# Examples.net
KiCad netlist of a schematic drawn in EAGLE
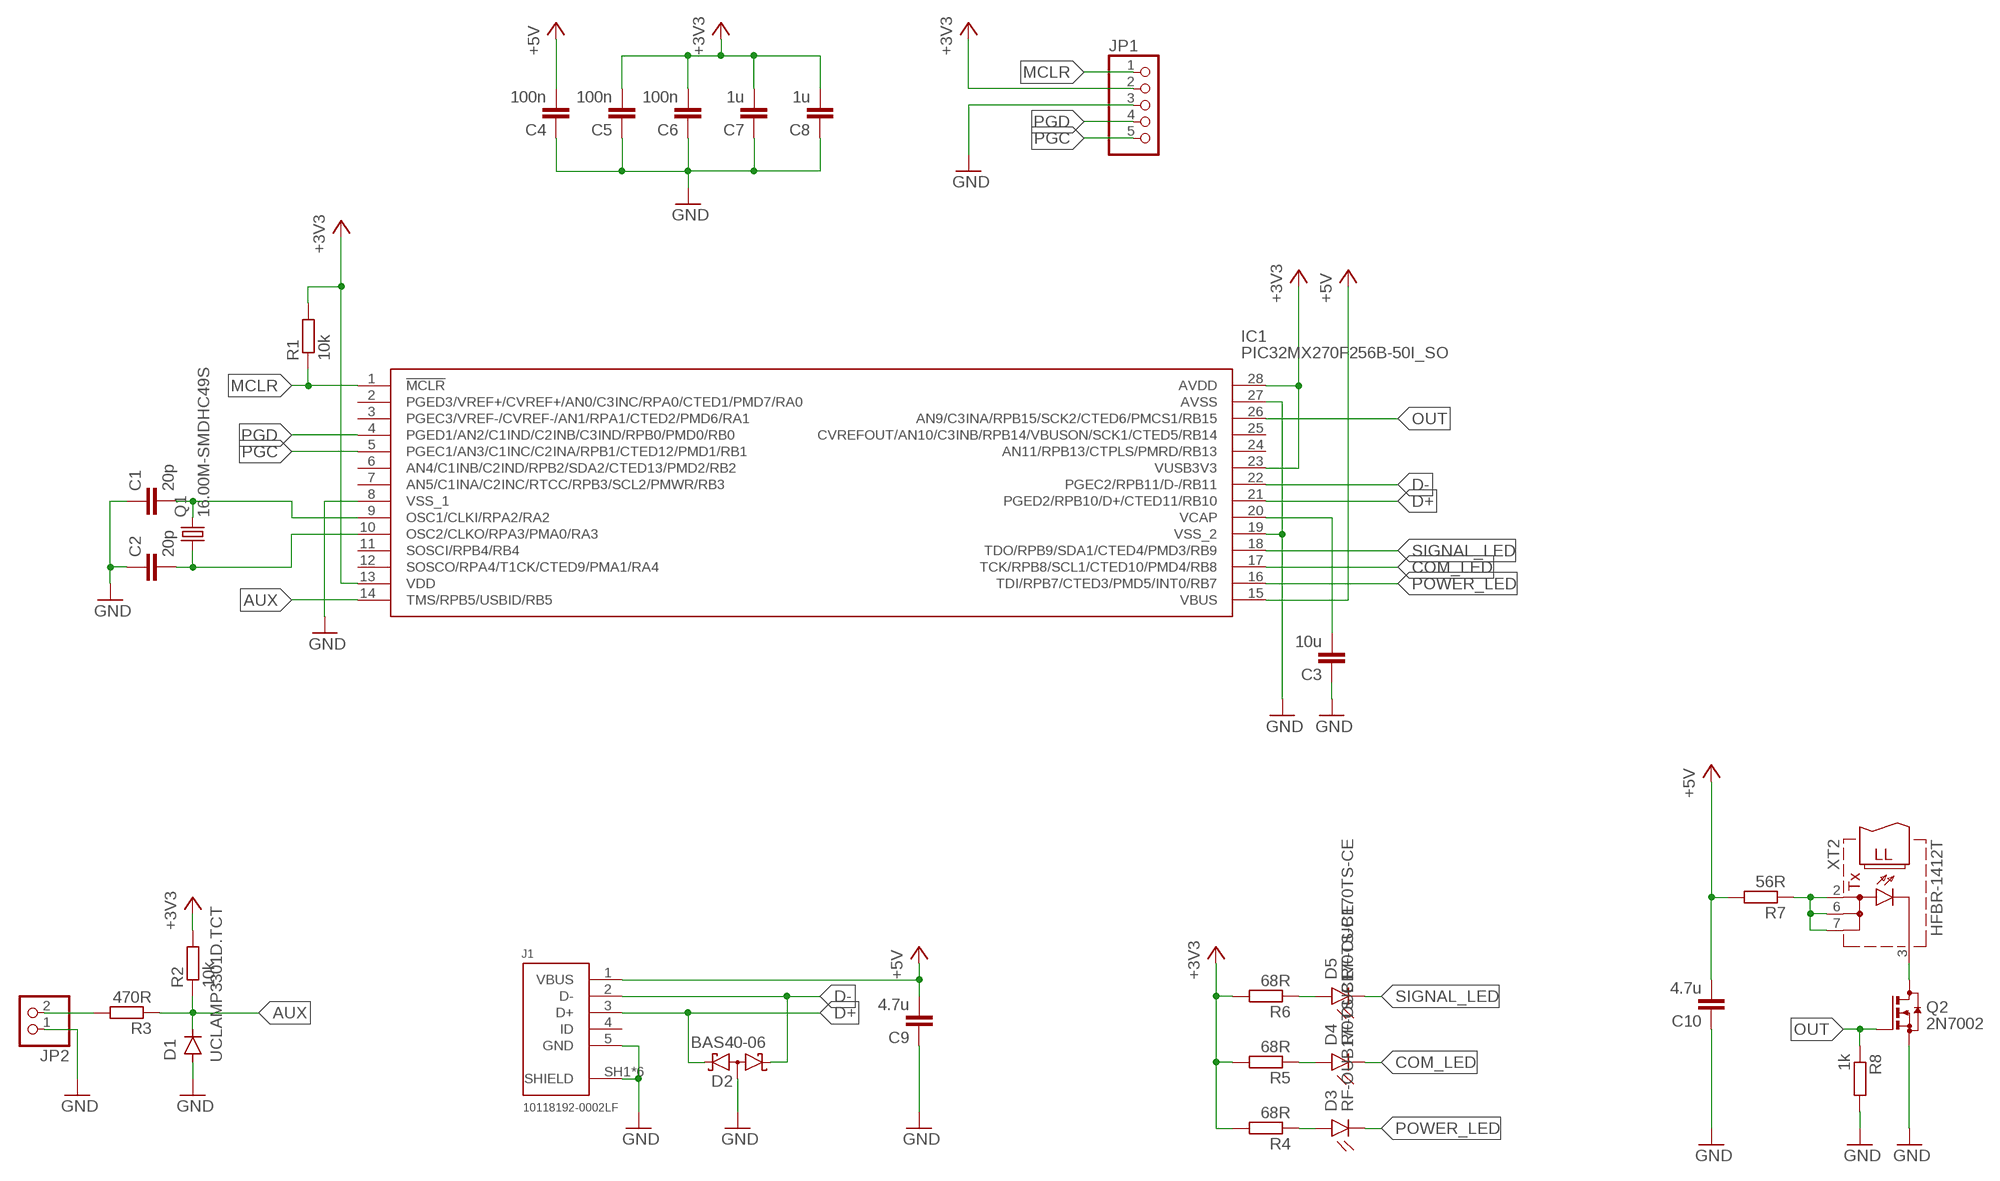
[diagram p0: schematic, sheet 1]

(export (version "E")
  (design (tool "Eeschema 10.0.6"))
  (components
    (comp (ref "C1")
      (value "20p")
      (footprint "eagle-import:C0805")
      (libsource (lib "eagle-import") (part "C-EUC0805"))
    )
    (comp (ref "C2")
      (value "20p")
      (footprint "eagle-import:C0805")
      (libsource (lib "eagle-import") (part "C-EUC0805"))
    )
    (comp (ref "C3")
      (value "10u")
      (footprint "eagle-import:C0805")
      (libsource (lib "eagle-import") (part "C-EUC0805"))
    )
    (comp (ref "C4")
      (value "100n")
      (footprint "eagle-import:C0805")
      (libsource (lib "eagle-import") (part "C-EUC0805"))
    )
    (comp (ref "C5")
      (value "100n")
      (footprint "eagle-import:C0805")
      (libsource (lib "eagle-import") (part "C-EUC0805"))
    )
    (comp (ref "C6")
      (value "100n")
      (footprint "eagle-import:C0805")
      (libsource (lib "eagle-import") (part "C-EUC0805"))
    )
    (comp (ref "C7")
      (value "1u")
      (footprint "eagle-import:C0805")
      (libsource (lib "eagle-import") (part "C-EUC0805"))
    )
    (comp (ref "C8")
      (value "1u")
      (footprint "eagle-import:C0805")
      (libsource (lib "eagle-import") (part "C-EUC0805"))
    )
    (comp (ref "C9")
      (value "4.7u")
      (footprint "eagle-import:C0805")
      (libsource (lib "eagle-import") (part "C-EUC0805"))
    )
    (comp (ref "C10")
      (value "4.7u")
      (footprint "eagle-import:C0805")
      (libsource (lib "eagle-import") (part "C-EUC0805"))
    )
    (comp (ref "D1")
      (value "UCLAMP3301D.TCT")
      (footprint "eagle-import:SOD-323")
      (fields
        (field (name "DIGIKEY_PART_NUMBER") "1N4148WSFSTR-ND")
        (field (name "MANUFACTURER") "Diodes Incorporated")
        (field (name "MPN") "1N4148WS")
        (field (name "CREATED_BY") "PCBLayout.com")
      )
      (libsource (lib "eagle-import") (part "1N4148WS"))
    )
    (comp (ref "D2")
      (value "BAS40-06")
      (footprint "eagle-import:SOT23")
      (libsource (lib "eagle-import") (part "BAS40-06"))
    )
    (comp (ref "D3")
      (value "RF-OUB170TS-CE")
      (footprint "eagle-import:LEDC2012X110N_FLAT-B")
      (libsource (lib "eagle-import") (part "CHIP-FLAT-B_0805"))
    )
    (comp (ref "D4")
      (value "RF-OUB170TS-CE")
      (footprint "eagle-import:LEDC2012X110N_FLAT-B")
      (libsource (lib "eagle-import") (part "CHIP-FLAT-B_0805"))
    )
    (comp (ref "D5")
      (value "RF-OUB170TS-CE")
      (footprint "eagle-import:LEDC2012X110N_FLAT-B")
      (libsource (lib "eagle-import") (part "CHIP-FLAT-B_0805"))
    )
    (comp (ref "IC1")
      (value "PIC32MX270F256B-50I_SO")
      (footprint "eagle-import:SOIC127P1030X265-28N")
      (fields
        (field (name "MANUFACTURER_PART_NUMBER") "PIC32MX270F256B-50I/SO")
        (field (name "MOUSER_PART_NUMBER") "579-32MX270F256B5ISO")
      )
      (libsource (lib "eagle-import") (part "PIC32MX270F256B-50I_SO"))
    )
    (comp (ref "J1")
      (value "10118192-0002LF")
      (footprint "eagle-import:10118192-0002LF")
      (fields
        (field (name "DIGIKEY_PARTNO") "609-5379-2-ND")
        (field (name "MANUFACTURER") "Amphenol ICC (FCI)")
        (field (name "CREATED_BY") "PCBLayout.com")
      )
      (libsource (lib "eagle-import") (part "10118192-0002LF"))
    )
    (comp (ref "JP1")
      (value "PINHD-1X5")
      (footprint "eagle-import:1X05")
      (libsource (lib "eagle-import") (part "PINHD-1X5"))
    )
    (comp (ref "JP2")
      (value "PINHD-1X2")
      (footprint "eagle-import:1X02")
      (libsource (lib "eagle-import") (part "PINHD-1X2"))
    )
    (comp (ref "Q1")
      (value "16.00M-SMDHC49S")
      (footprint "eagle-import:SM49")
      (libsource (lib "eagle-import") (part "CRYSTALSM49"))
    )
    (comp (ref "Q2")
      (value "2N7002")
      (footprint "eagle-import:SOT23")
      (libsource (lib "eagle-import") (part "BSS123"))
    )
    (comp (ref "R1")
      (value "10k")
      (footprint "eagle-import:R0805")
      (libsource (lib "eagle-import") (part "R-EU_R0805"))
    )
    (comp (ref "R2")
      (value "10k")
      (footprint "eagle-import:R0805")
      (libsource (lib "eagle-import") (part "R-EU_R0805"))
    )
    (comp (ref "R3")
      (value "470R")
      (footprint "eagle-import:R0805")
      (libsource (lib "eagle-import") (part "R-EU_R0805"))
    )
    (comp (ref "R4")
      (value "68R")
      (footprint "eagle-import:R0805")
      (libsource (lib "eagle-import") (part "R-EU_R0805"))
    )
    (comp (ref "R5")
      (value "68R")
      (footprint "eagle-import:R0805")
      (libsource (lib "eagle-import") (part "R-EU_R0805"))
    )
    (comp (ref "R6")
      (value "68R")
      (footprint "eagle-import:R0805")
      (libsource (lib "eagle-import") (part "R-EU_R0805"))
    )
    (comp (ref "R7")
      (value "56R")
      (footprint "eagle-import:R0805")
      (libsource (lib "eagle-import") (part "R-EU_R0805"))
    )
    (comp (ref "R8")
      (value "1k")
      (footprint "eagle-import:R0805")
      (libsource (lib "eagle-import") (part "R-EU_R0805"))
    )
    (comp (ref "XT2")
      (value "HFBR-1412T")
      (footprint "eagle-import:HFBR-X41XT")
      (fields (field (name "MF") "AGILENT TECHNOLOGIES"))
      (libsource (lib "eagle-import") (part "HFBR-1412T"))
    )
  )
  (nets
    (net (code "1") (name "+3V3") (class "Default")
      (node (ref "C5") (pin "2") (pinfunction "2_2") (pintype "passive"))
      (node (ref "C6") (pin "2") (pinfunction "2_2") (pintype "passive"))
      (node (ref "C7") (pin "2") (pinfunction "2_2") (pintype "passive"))
      (node (ref "C8") (pin "2") (pinfunction "2_2") (pintype "passive"))
      (node (ref "IC1") (pin "13") (pinfunction "VDD_13") (pintype "bidirectional"))
      (node (ref "IC1") (pin "23") (pinfunction "VUSB3V3_23") (pintype "bidirectional"))
      (node (ref "IC1") (pin "28") (pinfunction "AVDD_28") (pintype "bidirectional"))
      (node (ref "JP1") (pin "2") (pinfunction "2_2") (pintype "passive"))
      (node (ref "R1") (pin "2") (pinfunction "2_2") (pintype "passive"))
      (node (ref "R2") (pin "2") (pinfunction "2_2") (pintype "passive"))
      (node (ref "R4") (pin "2") (pinfunction "2_2") (pintype "passive"))
      (node (ref "R5") (pin "2") (pinfunction "2_2") (pintype "passive"))
      (node (ref "R6") (pin "2") (pinfunction "2_2") (pintype "passive"))
    )
    (net (code "2") (name "+5V") (class "Default")
      (node (ref "C10") (pin "2") (pinfunction "2_2") (pintype "passive"))
      (node (ref "C4") (pin "2") (pinfunction "2_2") (pintype "passive"))
      (node (ref "C9") (pin "2") (pinfunction "2_2") (pintype "passive"))
      (node (ref "IC1") (pin "15") (pinfunction "VBUS_15") (pintype "bidirectional"))
      (node (ref "J1") (pin "1") (pinfunction "VBUS_1") (pintype "passive"))
      (node (ref "R7") (pin "2") (pinfunction "2_2") (pintype "passive"))
    )
    (net (code "3") (name "AUX") (class "Default")
      (node (ref "D1") (pin "C") (pinfunction "C_C") (pintype "passive"))
      (node (ref "IC1") (pin "14") (pinfunction "TMS/RPB5/USBID/RB5_14") (pintype "bidirectional"))
      (node (ref "R2") (pin "1") (pinfunction "1_1") (pintype "passive"))
      (node (ref "R3") (pin "1") (pinfunction "1_1") (pintype "passive"))
    )
    (net (code "4") (name "COM_LED") (class "Default")
      (node (ref "D4") (pin "C") (pinfunction "C_C") (pintype "passive"))
      (node (ref "IC1") (pin "17") (pinfunction "TCK/RPB8/SCL1/CTED10/PMD4/RB8_17") (pintype "bidirectional"))
    )
    (net (code "5") (name "D+") (class "Default")
      (node (ref "D2") (pin "2") (pinfunction "K2_2") (pintype "passive"))
      (node (ref "IC1") (pin "21") (pinfunction "PGED2/RPB10/D+/CTED11/RB10_21") (pintype "bidirectional"))
      (node (ref "J1") (pin "3") (pinfunction "D+_3") (pintype "passive"))
    )
    (net (code "6") (name "D-") (class "Default")
      (node (ref "D2") (pin "1") (pinfunction "K1_1") (pintype "passive"))
      (node (ref "IC1") (pin "22") (pinfunction "PGEC2/RPB11/D-/RB11_22") (pintype "bidirectional"))
      (node (ref "J1") (pin "2") (pinfunction "D-_2") (pintype "passive"))
    )
    (net (code "7") (name "GND") (class "Default")
      (node (ref "C1") (pin "1") (pinfunction "1_1") (pintype "passive"))
      (node (ref "C10") (pin "1") (pinfunction "1_1") (pintype "passive"))
      (node (ref "C2") (pin "1") (pinfunction "1_1") (pintype "passive"))
      (node (ref "C3") (pin "1") (pinfunction "1_1") (pintype "passive"))
      (node (ref "C4") (pin "1") (pinfunction "1_1") (pintype "passive"))
      (node (ref "C5") (pin "1") (pinfunction "1_1") (pintype "passive"))
      (node (ref "C6") (pin "1") (pinfunction "1_1") (pintype "passive"))
      (node (ref "C7") (pin "1") (pinfunction "1_1") (pintype "passive"))
      (node (ref "C8") (pin "1") (pinfunction "1_1") (pintype "passive"))
      (node (ref "C9") (pin "1") (pinfunction "1_1") (pintype "passive"))
      (node (ref "D1") (pin "A") (pinfunction "A_A") (pintype "passive"))
      (node (ref "D2") (pin "3") (pinfunction "AA_3") (pintype "passive"))
      (node (ref "IC1") (pin "19") (pinfunction "VSS_2_19") (pintype "bidirectional"))
      (node (ref "IC1") (pin "27") (pinfunction "AVSS_27") (pintype "bidirectional"))
      (node (ref "IC1") (pin "8") (pinfunction "VSS_1_8") (pintype "bidirectional"))
      (node (ref "J1") (pin "5") (pinfunction "GND_5") (pintype "passive"))
      (node (ref "J1") (pin "SH1") (pinfunction "SHIELD_SH1") (pintype "power_in"))
      (node (ref "J1") (pin "SH2") (pinfunction "SHIELD_SH2") (pintype "power_in"))
      (node (ref "J1") (pin "SH3") (pinfunction "SHIELD_SH3") (pintype "power_in"))
      (node (ref "J1") (pin "SH4") (pinfunction "SHIELD_SH4") (pintype "power_in"))
      (node (ref "J1") (pin "SH5") (pinfunction "SHIELD_SH5") (pintype "power_in"))
      (node (ref "J1") (pin "SH6") (pinfunction "SHIELD_SH6") (pintype "power_in"))
      (node (ref "JP1") (pin "3") (pinfunction "3_3") (pintype "passive"))
      (node (ref "JP2") (pin "1") (pinfunction "1_1") (pintype "passive"))
      (node (ref "Q2") (pin "2") (pinfunction "S_2") (pintype "passive"))
      (node (ref "R8") (pin "2") (pinfunction "2_2") (pintype "passive"))
    )
    (net (code "8") (name "MCLR") (class "Default")
      (node (ref "IC1") (pin "1") (pinfunction "~{MCLR}_1") (pintype "bidirectional"))
      (node (ref "JP1") (pin "1") (pinfunction "1_1") (pintype "passive"))
      (node (ref "R1") (pin "1") (pinfunction "1_1") (pintype "passive"))
    )
    (net (code "9") (name "Net-(D3-PadA)") (class "Default")
      (node (ref "D3") (pin "A") (pinfunction "A_A") (pintype "passive"))
      (node (ref "R4") (pin "1") (pinfunction "1_1") (pintype "passive"))
    )
    (net (code "10") (name "Net-(D4-PadA)") (class "Default")
      (node (ref "D4") (pin "A") (pinfunction "A_A") (pintype "passive"))
      (node (ref "R5") (pin "1") (pinfunction "1_1") (pintype "passive"))
    )
    (net (code "11") (name "Net-(D5-PadA)") (class "Default")
      (node (ref "D5") (pin "A") (pinfunction "A_A") (pintype "passive"))
      (node (ref "R6") (pin "1") (pinfunction "1_1") (pintype "passive"))
    )
    (net (code "12") (name "Net-(IC1-OSC1{slash}CLKI{slash}RPA2{slash}RA2)") (class "Default")
      (node (ref "C1") (pin "2") (pinfunction "2_2") (pintype "passive"))
      (node (ref "IC1") (pin "9") (pinfunction "OSC1/CLKI/RPA2/RA2_9") (pintype "bidirectional"))
      (node (ref "Q1") (pin "2") (pinfunction "2_2") (pintype "passive"))
    )
    (net (code "13") (name "Net-(IC1-OSC2{slash}CLKO{slash}RPA3{slash}PMA0{slash}RA3)") (class "Default")
      (node (ref "C2") (pin "2") (pinfunction "2_2") (pintype "passive"))
      (node (ref "IC1") (pin "10") (pinfunction "OSC2/CLKO/RPA3/PMA0/RA3_10") (pintype "bidirectional"))
      (node (ref "Q1") (pin "1") (pinfunction "1_1") (pintype "passive"))
    )
    (net (code "14") (name "Net-(IC1-VCAP)") (class "Default")
      (node (ref "C3") (pin "2") (pinfunction "2_2") (pintype "passive"))
      (node (ref "IC1") (pin "20") (pinfunction "VCAP_20") (pintype "bidirectional"))
    )
    (net (code "15") (name "Net-(JP2-Pad2)") (class "Default")
      (node (ref "JP2") (pin "2") (pinfunction "2_2") (pintype "passive"))
      (node (ref "R3") (pin "2") (pinfunction "2_2") (pintype "passive"))
    )
    (net (code "16") (name "Net-(Q2-D)") (class "Default")
      (node (ref "Q2") (pin "3") (pinfunction "D_3") (pintype "passive"))
      (node (ref "XT2") (pin "3") (pinfunction "C_3") (pintype "passive"))
    )
    (net (code "17") (name "Net-(XT2-A)") (class "Default")
      (node (ref "R7") (pin "1") (pinfunction "1_1") (pintype "passive"))
      (node (ref "XT2") (pin "2") (pinfunction "A_2") (pintype "passive"))
      (node (ref "XT2") (pin "6") (pinfunction "A1_6") (pintype "passive"))
      (node (ref "XT2") (pin "7") (pinfunction "A2_7") (pintype "passive"))
    )
    (net (code "18") (name "OUT") (class "Default")
      (node (ref "IC1") (pin "26") (pinfunction "AN9/C3INA/RPB15/SCK2/CTED6/PMCS1/RB15_26") (pintype "bidirectional"))
      (node (ref "Q2") (pin "1") (pinfunction "G_1") (pintype "passive"))
      (node (ref "R8") (pin "1") (pinfunction "1_1") (pintype "passive"))
    )
    (net (code "19") (name "PGC") (class "Default")
      (node (ref "IC1") (pin "5") (pinfunction "PGEC1/AN3/C1INC/C2INA/RPB1/CTED12/PMD1/RB1_5") (pintype "bidirectional"))
      (node (ref "JP1") (pin "5") (pinfunction "5_5") (pintype "passive"))
    )
    (net (code "20") (name "PGD") (class "Default")
      (node (ref "IC1") (pin "4") (pinfunction "PGED1/AN2/C1IND/C2INB/C3IND/RPB0/PMD0/RB0_4") (pintype "bidirectional"))
      (node (ref "JP1") (pin "4") (pinfunction "4_4") (pintype "passive"))
    )
    (net (code "21") (name "POWER_LED") (class "Default")
      (node (ref "D3") (pin "C") (pinfunction "C_C") (pintype "passive"))
      (node (ref "IC1") (pin "16") (pinfunction "TDI/RPB7/CTED3/PMD5/INT0/RB7_16") (pintype "bidirectional"))
    )
    (net (code "22") (name "SIGNAL_LED") (class "Default")
      (node (ref "D5") (pin "C") (pinfunction "C_C") (pintype "passive"))
      (node (ref "IC1") (pin "18") (pinfunction "TDO/RPB9/SDA1/CTED4/PMD3/RB9_18") (pintype "bidirectional"))
    )
    (net (code "23") (name "unconnected-(IC1-AN4{slash}C1INB{slash}C2IND{slash}RPB2{slash}SDA2{slash}CTED13{slash}PMD2{slash}RB2-Pad6)") (class "Default")
      (node (ref "IC1") (pin "6") (pinfunction "AN4/C1INB/C2IND/RPB2/SDA2/CTED13/PMD2/RB2_6") (pintype "bidirectional"))
    )
    (net (code "24") (name "unconnected-(IC1-AN5{slash}C1INA{slash}C2INC{slash}RTCC{slash}RPB3{slash}SCL2{slash}PMWR{slash}RB3-Pad7)") (class "Default")
      (node (ref "IC1") (pin "7") (pinfunction "AN5/C1INA/C2INC/RTCC/RPB3/SCL2/PMWR/RB3_7") (pintype "bidirectional"))
    )
    (net (code "25") (name "unconnected-(IC1-AN11{slash}RPB13{slash}CTPLS{slash}PMRD{slash}RB13-Pad24)") (class "Default")
      (node (ref "IC1") (pin "24") (pinfunction "AN11/RPB13/CTPLS/PMRD/RB13_24") (pintype "bidirectional"))
    )
    (net (code "26") (name "unconnected-(IC1-CVREFOUT{slash}AN10{slash}C3INB{slash}RPB14{slash}VBUSON{slash}SCK1{slash}CTED5{slash}RB14-Pad25)") (class "Default")
      (node (ref "IC1") (pin "25") (pinfunction "CVREFOUT/AN10/C3INB/RPB14/VBUSON/SCK1/CTED5/RB14_25") (pintype "bidirectional"))
    )
    (net (code "27") (name "unconnected-(IC1-PGEC3{slash}VREF-{slash}CVREF-{slash}AN1{slash}RPA1{slash}CTED2{slash}PMD6{slash}RA1-Pad3)") (class "Default")
      (node (ref "IC1") (pin "3") (pinfunction "PGEC3/VREF-/CVREF-/AN1/RPA1/CTED2/PMD6/RA1_3") (pintype "bidirectional"))
    )
    (net (code "28") (name "unconnected-(IC1-PGED3{slash}VREF+{slash}CVREF+{slash}AN0{slash}C3INC{slash}RPA0{slash}CTED1{slash}PMD7{slash}RA0-Pad2)") (class "Default")
      (node (ref "IC1") (pin "2") (pinfunction "PGED3/VREF+/CVREF+/AN0/C3INC/RPA0/CTED1/PMD7/RA0_2") (pintype "bidirectional"))
    )
    (net (code "29") (name "unconnected-(IC1-SOSCI{slash}RPB4{slash}RB4-Pad11)") (class "Default")
      (node (ref "IC1") (pin "11") (pinfunction "SOSCI/RPB4/RB4_11") (pintype "bidirectional"))
    )
    (net (code "30") (name "unconnected-(IC1-SOSCO{slash}RPA4{slash}T1CK{slash}CTED9{slash}PMA1{slash}RA4-Pad12)") (class "Default")
      (node (ref "IC1") (pin "12") (pinfunction "SOSCO/RPA4/T1CK/CTED9/PMA1/RA4_12") (pintype "bidirectional"))
    )
    (net (code "31") (name "unconnected-(J1-ID-Pad4)") (class "Default")
      (node (ref "J1") (pin "4") (pinfunction "ID_4") (pintype "passive"))
    )
  )
)
